# ProPrj_usb__2025-12-06-21-05-20.net
KiCad netlist of a schematic drawn in EasyEDA Pro
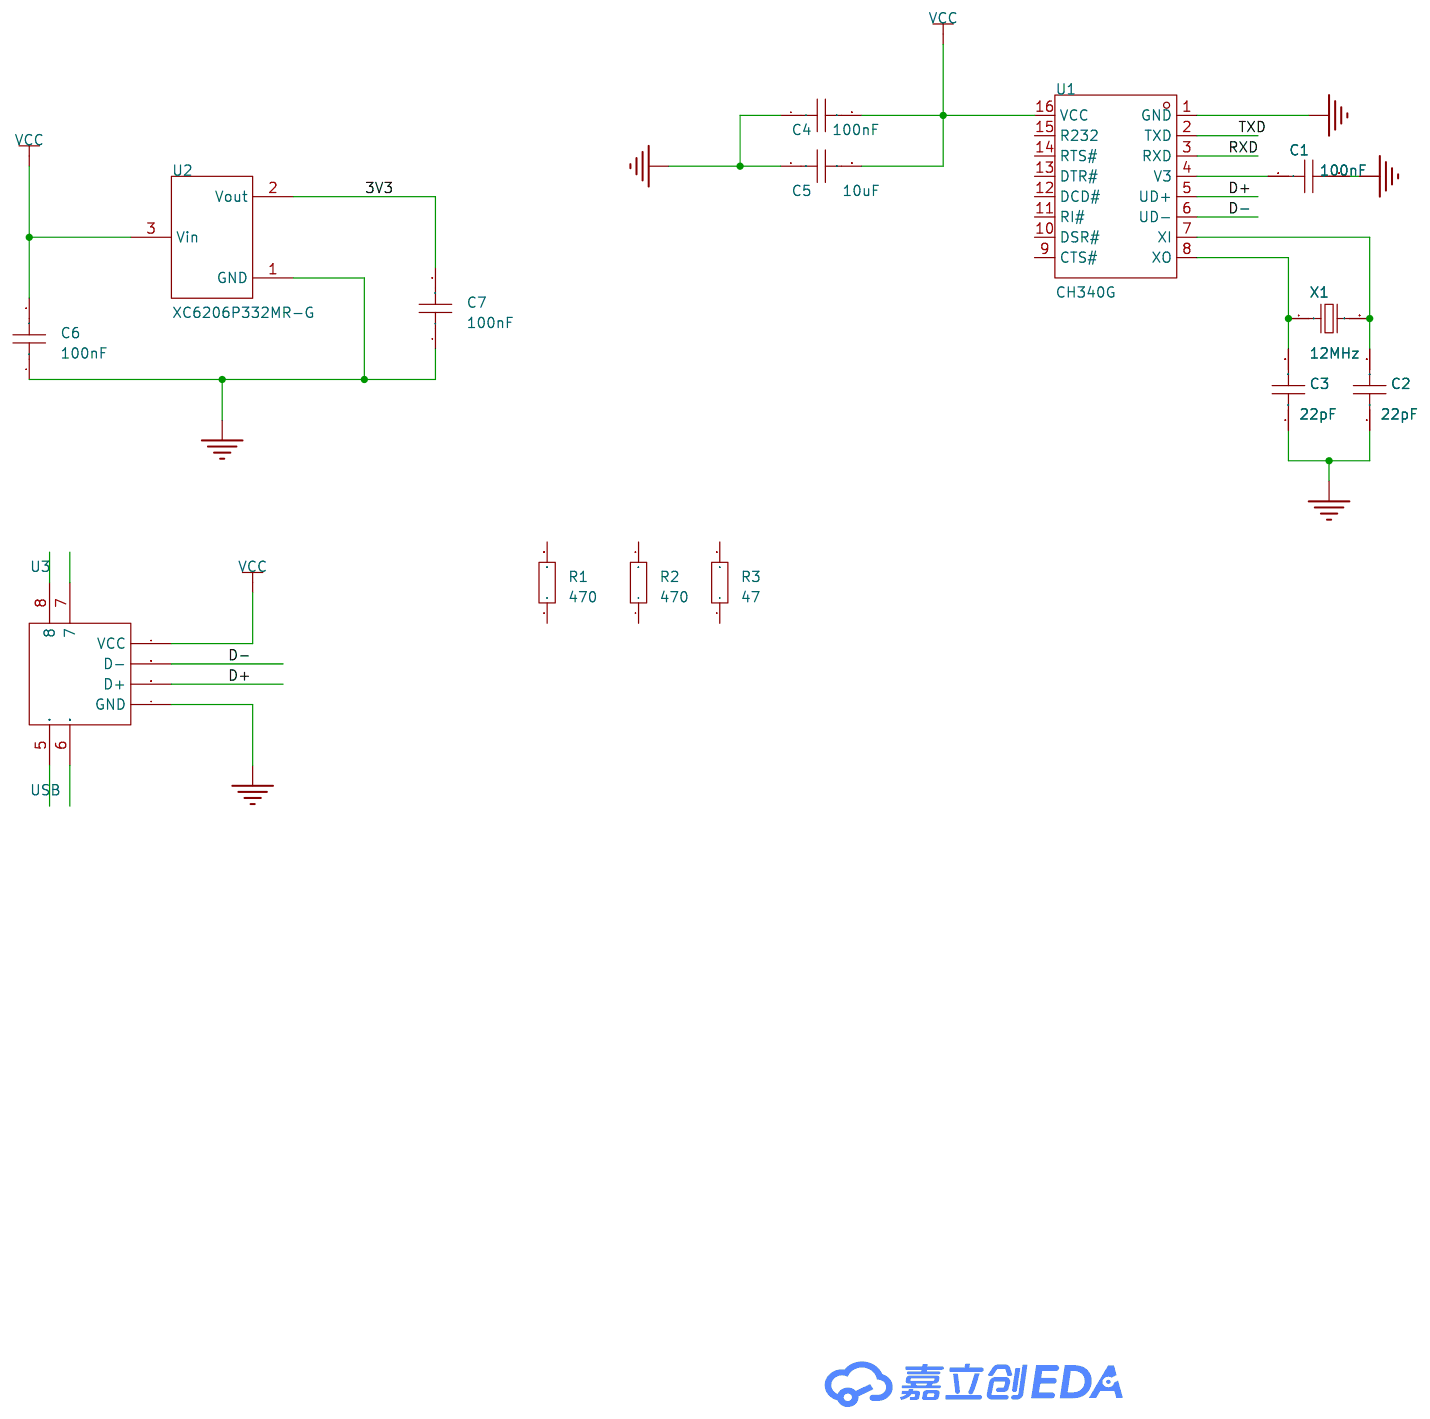
[diagram p0: schematic sheet]

(export (version "E")
  (design (tool "Eeschema 10.0.6"))
  (components
    (comp (ref "C1")
      (value "100nF")
      (footprint "easyedapro:C0603")
      (libsource (lib "easyedapro") (part "Capacitance"))
    )
    (comp (ref "C2")
      (value "22pF")
      (footprint "easyedapro:C0603")
      (libsource (lib "easyedapro") (part "Capacitance"))
    )
    (comp (ref "C3")
      (value "22pF")
      (footprint "easyedapro:C0603")
      (libsource (lib "easyedapro") (part "Capacitance"))
    )
    (comp (ref "C4")
      (value "100nF")
      (footprint "easyedapro:C0603")
      (libsource (lib "easyedapro") (part "Capacitance"))
    )
    (comp (ref "C5")
      (value "10uF")
      (footprint "easyedapro:C0603")
      (libsource (lib "easyedapro") (part "Capacitance"))
    )
    (comp (ref "C6")
      (value "100nF")
      (footprint "easyedapro:C0603")
      (libsource (lib "easyedapro") (part "Capacitance"))
    )
    (comp (ref "C7")
      (value "100nF")
      (footprint "easyedapro:C0603")
      (libsource (lib "easyedapro") (part "Capacitance"))
    )
    (comp (ref "R1") (value "470") (footprint "easyedapro:R0603") (libsource (lib "easyedapro") (part "电阻")))
    (comp (ref "R2") (value "470") (footprint "easyedapro:R0603") (libsource (lib "easyedapro") (part "电阻")))
    (comp (ref "R3") (value "47") (footprint "easyedapro:R0603") (libsource (lib "easyedapro") (part "电阻")))
    (comp (ref "U1")
      (value "CH340G")
      (footprint "easyedapro:SOIC-16_L9.9-W3.9-P1.27-LS6.0-BL")
      (description "应用功能:USB转UART;接口协议:USB 2.0;数据速率:2Mbps;")
      (fields (field (name "Manufacturer") "WCH(南京沁恒)"))
      (libsource (lib "easyedapro") (part "CH340G"))
    )
    (comp (ref "U2")
      (value "XC6206P332MR-G")
      (footprint "easyedapro:SOT-23-3_L2.9-W1.6-P1.90-LS2.8-BR")
      (description "输出类型:固定;工作电压:6V;输出电压:3.3V;输出电流:200mA;电源纹波抑制比(PSRR):-;输出极性:正极;")
      (fields (field (name "Manufacturer") "TOREX(特瑞仕)"))
      (libsource (lib "easyedapro") (part "XC6206P332MR"))
    )
    (comp (ref "U3")
      (value "USB")
      (footprint "easyedapro:USB-SMD_USB_1")
      (libsource (lib "easyedapro") (part "USB"))
    )
    (comp (ref "X1")
      (value "12MHz")
      (footprint "easyedapro:CRYSTAL-SMD_L5.0-W3.2")
      (description "晶振类型:贴片晶振;频率:12MHz;常温频差:±20ppm;负载电容:20pF;频率稳定度:±30ppm;")
      (fields
        (field (name "Manufacturer Part") "XC53G2-12.000-F20LJDT")
        (field (name "Manufacturer") "HCI(杭晶)")
      )
      (libsource (lib "easyedapro") (part "XC53G2-12.000-F20LJDT"))
    )
  )
  (nets
    (net (code "1") (name "/3V3") (class "Default")
      (node (ref "C7") (pin "2") (pinfunction "2_2") (pintype "input"))
      (node (ref "U2") (pin "2") (pinfunction "Vout_2") (pintype "unspecified"))
    )
    (net (code "2") (name "/D+") (class "Default")
      (node (ref "U1") (pin "5") (pinfunction "UD+_5") (pintype "unspecified"))
      (node (ref "U3") (pin "3") (pinfunction "D+_3") (pintype "input"))
    )
    (net (code "3") (name "/D-") (class "Default")
      (node (ref "U1") (pin "6") (pinfunction "UD-_6") (pintype "unspecified"))
      (node (ref "U3") (pin "2") (pinfunction "D-_2") (pintype "input"))
    )
    (net (code "4") (name "/RXD") (class "Default")
      (node (ref "U1") (pin "3") (pinfunction "RXD_3") (pintype "unspecified"))
    )
    (net (code "5") (name "/TXD") (class "Default")
      (node (ref "U1") (pin "2") (pinfunction "TXD_2") (pintype "unspecified"))
    )
    (net (code "6") (name "GND") (class "Default")
      (node (ref "C1") (pin "2") (pinfunction "2_2") (pintype "input"))
      (node (ref "C2") (pin "1") (pinfunction "1_1") (pintype "input"))
      (node (ref "C3") (pin "1") (pinfunction "1_1") (pintype "input"))
      (node (ref "C4") (pin "1") (pinfunction "1_1") (pintype "input"))
      (node (ref "C5") (pin "1") (pinfunction "1_1") (pintype "input"))
      (node (ref "C6") (pin "1") (pinfunction "1_1") (pintype "input"))
      (node (ref "C7") (pin "1") (pinfunction "1_1") (pintype "input"))
      (node (ref "U1") (pin "1") (pinfunction "GND_1") (pintype "unspecified"))
      (node (ref "U2") (pin "1") (pinfunction "GND_1") (pintype "unspecified"))
      (node (ref "U3") (pin "4") (pinfunction "GND_4") (pintype "input"))
    )
    (net (code "7") (name "Net-(U1-V3)") (class "Default")
      (node (ref "C1") (pin "1") (pinfunction "1_1") (pintype "input"))
      (node (ref "U1") (pin "4") (pinfunction "V3_4") (pintype "unspecified"))
    )
    (net (code "8") (name "Net-(U1-XI)") (class "Default")
      (node (ref "C2") (pin "2") (pinfunction "2_2") (pintype "input"))
      (node (ref "U1") (pin "7") (pinfunction "XI_7") (pintype "unspecified"))
      (node (ref "X1") (pin "2") (pinfunction "2_2") (pintype "unspecified"))
    )
    (net (code "9") (name "Net-(U1-XO)") (class "Default")
      (node (ref "C3") (pin "2") (pinfunction "2_2") (pintype "input"))
      (node (ref "U1") (pin "8") (pinfunction "XO_8") (pintype "unspecified"))
      (node (ref "X1") (pin "1") (pinfunction "1_1") (pintype "unspecified"))
    )
    (net (code "10") (name "VCC") (class "Default")
      (node (ref "C4") (pin "2") (pinfunction "2_2") (pintype "input"))
      (node (ref "C5") (pin "2") (pinfunction "2_2") (pintype "input"))
      (node (ref "C6") (pin "2") (pinfunction "2_2") (pintype "input"))
      (node (ref "U1") (pin "16") (pinfunction "VCC_16") (pintype "unspecified"))
      (node (ref "U2") (pin "3") (pinfunction "Vin_3") (pintype "unspecified"))
      (node (ref "U3") (pin "1") (pinfunction "VCC_1") (pintype "input"))
    )
    (net (code "11") (name "unconnected-(R1-Pad1)") (class "Default")
      (node (ref "R1") (pin "1") (pinfunction "1_1") (pintype "input"))
    )
    (net (code "12") (name "unconnected-(R1-Pad2)") (class "Default")
      (node (ref "R1") (pin "2") (pinfunction "2_2") (pintype "input"))
    )
    (net (code "13") (name "unconnected-(R2-Pad1)") (class "Default")
      (node (ref "R2") (pin "1") (pinfunction "1_1") (pintype "input"))
    )
    (net (code "14") (name "unconnected-(R2-Pad2)") (class "Default")
      (node (ref "R2") (pin "2") (pinfunction "2_2") (pintype "input"))
    )
    (net (code "15") (name "unconnected-(R3-Pad1)") (class "Default")
      (node (ref "R3") (pin "1") (pinfunction "1_1") (pintype "input"))
    )
    (net (code "16") (name "unconnected-(R3-Pad2)") (class "Default")
      (node (ref "R3") (pin "2") (pinfunction "2_2") (pintype "input"))
    )
    (net (code "17") (name "unconnected-(U1-CTS#-Pad9)") (class "Default")
      (node (ref "U1") (pin "9") (pinfunction "CTS#_9") (pintype "unspecified"))
    )
    (net (code "18") (name "unconnected-(U1-DCD#-Pad12)") (class "Default")
      (node (ref "U1") (pin "12") (pinfunction "DCD#_12") (pintype "unspecified"))
    )
    (net (code "19") (name "unconnected-(U1-DSR#-Pad10)") (class "Default")
      (node (ref "U1") (pin "10") (pinfunction "DSR#_10") (pintype "unspecified"))
    )
    (net (code "20") (name "unconnected-(U1-DTR#-Pad13)") (class "Default")
      (node (ref "U1") (pin "13") (pinfunction "DTR#_13") (pintype "unspecified"))
    )
    (net (code "21") (name "unconnected-(U1-R232-Pad15)") (class "Default")
      (node (ref "U1") (pin "15") (pinfunction "R232_15") (pintype "unspecified"))
    )
    (net (code "22") (name "unconnected-(U1-RI#-Pad11)") (class "Default")
      (node (ref "U1") (pin "11") (pinfunction "RI#_11") (pintype "unspecified"))
    )
    (net (code "23") (name "unconnected-(U1-RTS#-Pad14)") (class "Default")
      (node (ref "U1") (pin "14") (pinfunction "RTS#_14") (pintype "unspecified"))
    )
    (net (code "24") (name "unconnected-(U3-Pad7)") (class "Default")
      (node (ref "U3") (pin "7") (pinfunction "7_7") (pintype "unspecified"))
    )
    (net (code "25") (name "unconnected-(U3-Pad8)") (class "Default")
      (node (ref "U3") (pin "8") (pinfunction "8_8") (pintype "unspecified"))
    )
    (net (code "26") (name "unconnected-(U3-SH1-Pad5)") (class "Default")
      (node (ref "U3") (pin "5") (pinfunction "SH1_5") (pintype "unspecified"))
    )
    (net (code "27") (name "unconnected-(U3-SH2-Pad6)") (class "Default")
      (node (ref "U3") (pin "6") (pinfunction "SH2_6") (pintype "unspecified"))
    )
  )
)
